# Sheet2.net
KiCad netlist of a schematic drawn in Altium Designer
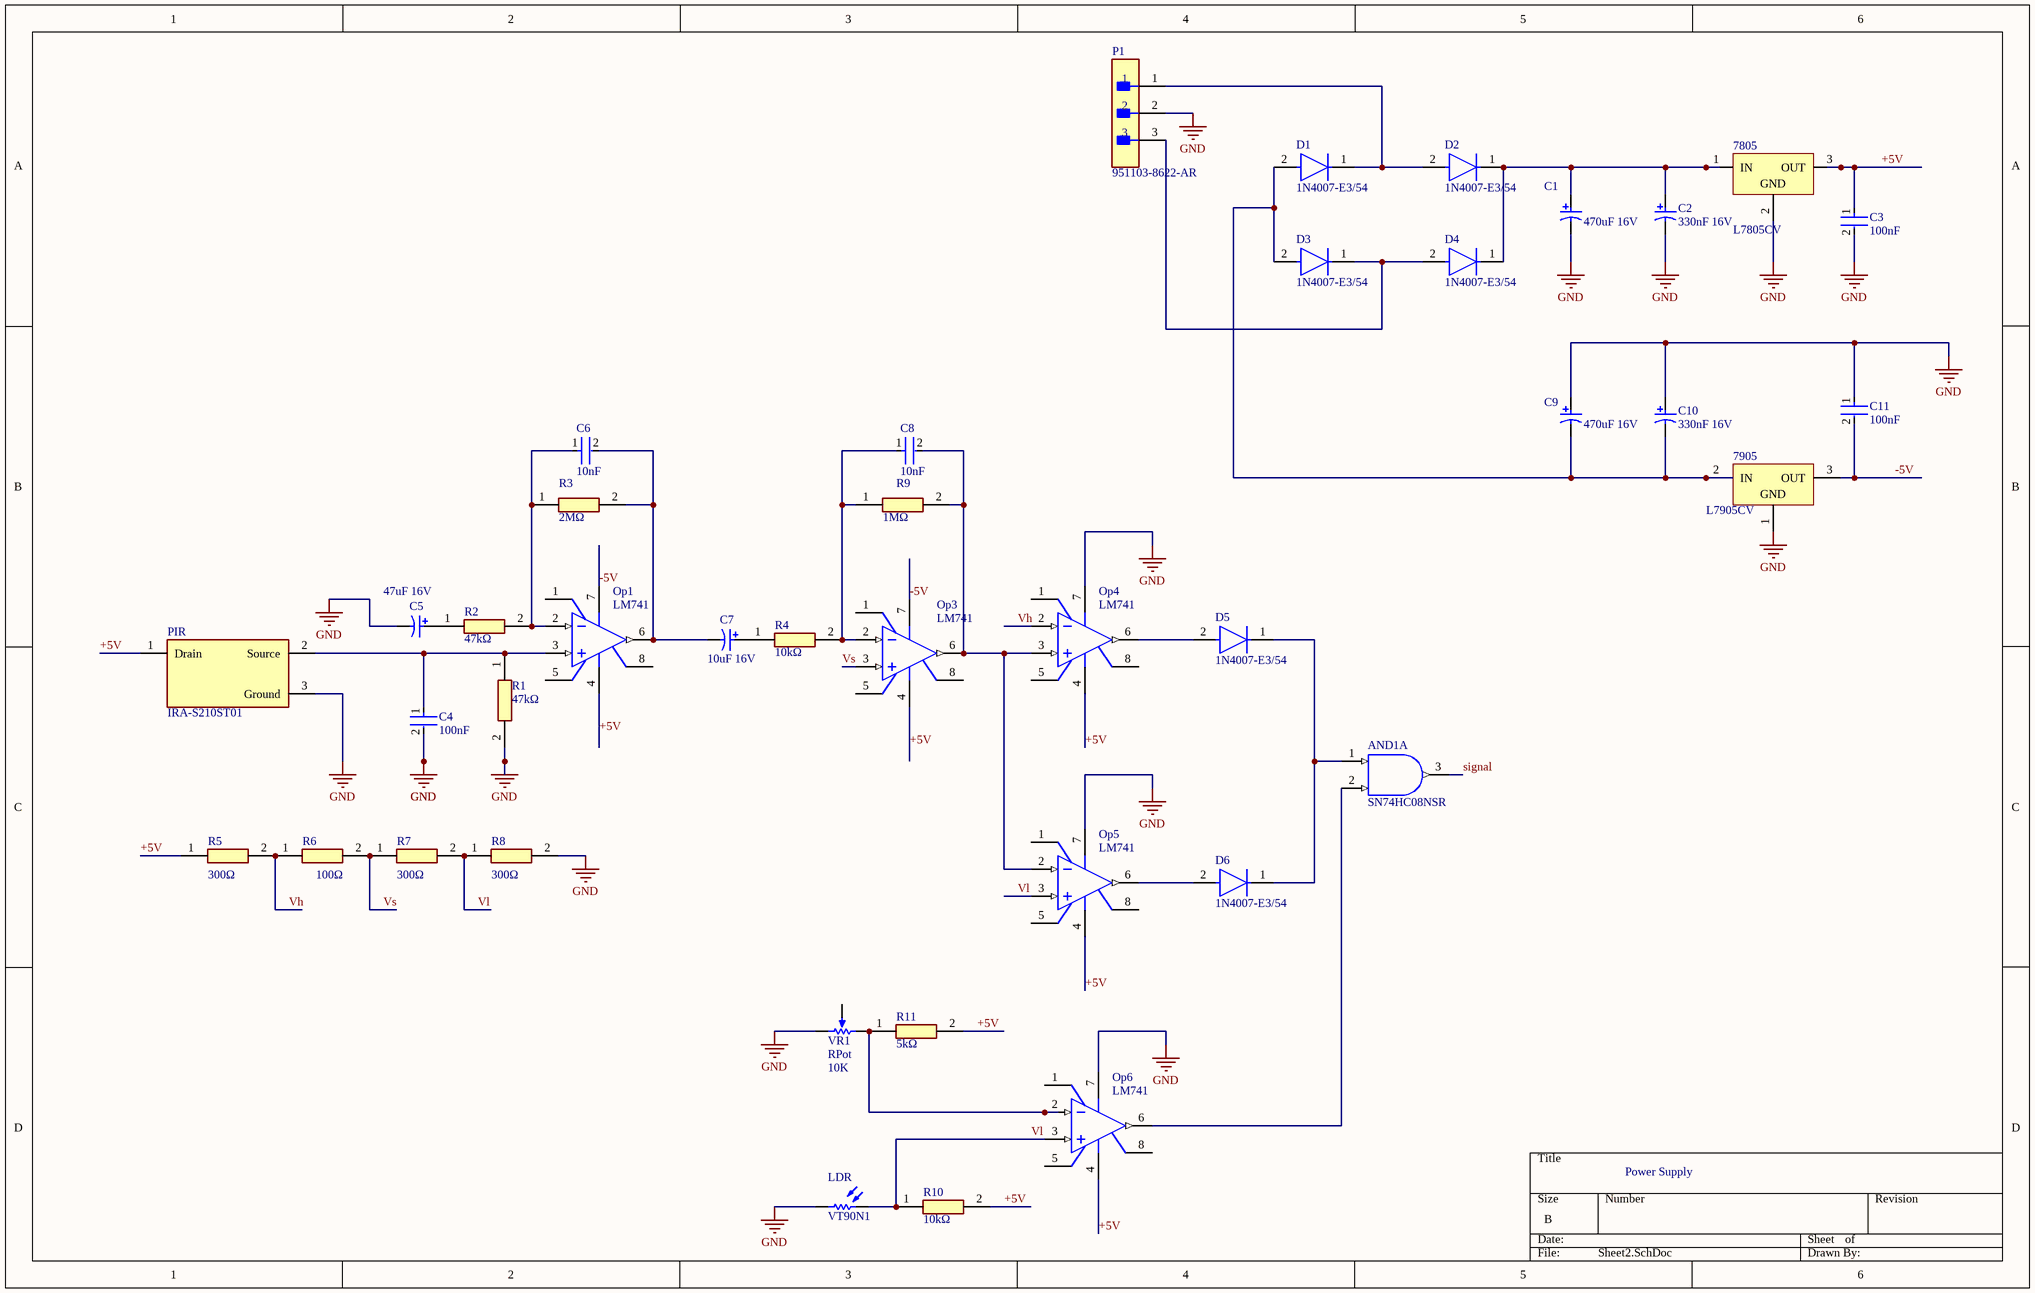
[diagram p0: Sheet2.SchDoc]

(export (version "E")
  (design (tool "Eeschema 10.0.6"))
  (components
    (comp (ref "7805")
      (value "L7805CV")
      (footprint "TO220")
      (description "Positive Voltage Regulator, 5V, 3-Pin TO-220")
      (libsource (lib "Altium Content Vault") (part "PM-REG-L4940-SIL3"))
    )
    (comp (ref "7905")
      (value "L7905CV")
      (footprint "TO-220")
      (description "Negative Voltage Regulator, -5V, 3-Pin TO-220")
      (libsource (lib "Altium Content Vault") (part "PM-REG-7905-SIL3"))
    )
    (comp (ref "AND1")
      (value "SN74HC08NSR")
      (footprint "NS0014A_M")
      (description "Quadruple 2-Input Positive-AND Gates, NS0014A, LARGE T&R")
      (fields
        (field (name "GENERIC PART NUMBER") "SN74HC08")
        (field (name "MANUFACTURER") "Texas Instruments")
      )
      (libsource (lib "Altium Content Vault") (part "TI-AND-4-2IN-14"))
    )
    (comp (ref "C1")
      (value "470uF 16V")
      (footprint "CAPPR65-350-1150X800X1250")
      (description "Aluminum Electrolytic Capacitor, 100 uF, +/- 20%, 50 V, -40 to 85 degC, 2-Pin THD, RoHS, Bulk")
      (fields (field (name "MANUFACTURER") "Panasonic") (field (name "VOLTAGE") "50V"))
      (libsource (lib "Altium Content Vault") (part "CAP-P-2"))
    )
    (comp (ref "C2")
      (value "330nF 16V")
      (footprint "CAPPR65-350-1150X800X1250")
      (description "Aluminum Electrolytic Capacitor, 100 uF, +/- 20%, 50 V, -40 to 85 degC, 2-Pin THD, RoHS, Bulk")
      (fields (field (name "MANUFACTURER") "Panasonic") (field (name "VOLTAGE") "50V"))
      (libsource (lib "Altium Content Vault") (part "CAP-P-2"))
    )
    (comp (ref "C3")
      (value "100nF")
      (footprint "FP-K15H5-MFG")
      (description "CAP CER 0.1UF 50V X7R RADIAL")
      (fields (field (name "VOLTAGE") "50V") (field (name "TOLERANCE") "10%"))
      (libsource (lib "Altium Content Vault") (part "11868f565c42a9108669ba33697ecf6"))
    )
    (comp (ref "C4")
      (value "100nF")
      (footprint "FP-K15H5-MFG")
      (description "CAP CER 0.1UF 50V X7R RADIAL")
      (fields (field (name "VOLTAGE") "50V") (field (name "TOLERANCE") "10%"))
      (libsource (lib "Altium Content Vault") (part "11868f565c42a9108669ba33697ecf6"))
    )
    (comp (ref "C5")
      (value "47uF 16V")
      (footprint "CAPPR65-350-1150X800X1250")
      (description "Aluminum Electrolytic Capacitor, 100 uF, +/- 20%, 50 V, -40 to 85 degC, 2-Pin THD, RoHS, Bulk")
      (fields (field (name "MANUFACTURER") "Panasonic") (field (name "VOLTAGE") "50V"))
      (libsource (lib "Altium Content Vault") (part "CAP-P-2"))
    )
    (comp (ref "C6")
      (value "10nF")
      (footprint "FP-K15H5-MFG")
      (description "CAP CER 0.1UF 50V X7R RADIAL")
      (fields (field (name "VOLTAGE") "50V") (field (name "TOLERANCE") "10%"))
      (libsource (lib "Altium Content Vault") (part "11868f565c42a9108669ba33697ecf6"))
    )
    (comp (ref "C7")
      (value "10uF 16V")
      (footprint "CAPPR65-350-1150X800X1250")
      (description "Aluminum Electrolytic Capacitor, 100 uF, +/- 20%, 50 V, -40 to 85 degC, 2-Pin THD, RoHS, Bulk")
      (fields (field (name "MANUFACTURER") "Panasonic") (field (name "VOLTAGE") "50V"))
      (libsource (lib "Altium Content Vault") (part "CAP-P-2"))
    )
    (comp (ref "C8")
      (value "10nF")
      (footprint "FP-K15H5-MFG")
      (description "CAP CER 0.1UF 50V X7R RADIAL")
      (fields (field (name "VOLTAGE") "50V") (field (name "TOLERANCE") "10%"))
      (libsource (lib "Altium Content Vault") (part "11868f565c42a9108669ba33697ecf6"))
    )
    (comp (ref "C9")
      (value "470uF 16V")
      (footprint "CAPPR65-350-1150X800X1250")
      (description "Aluminum Electrolytic Capacitor, 100 uF, +/- 20%, 50 V, -40 to 85 degC, 2-Pin THD, RoHS, Bulk")
      (fields (field (name "MANUFACTURER") "Panasonic") (field (name "VOLTAGE") "50V"))
      (libsource (lib "Altium Content Vault") (part "CAP-P-2"))
    )
    (comp (ref "C10")
      (value "330nF 16V")
      (footprint "CAPPR65-350-1150X800X1250")
      (description "Aluminum Electrolytic Capacitor, 100 uF, +/- 20%, 50 V, -40 to 85 degC, 2-Pin THD, RoHS, Bulk")
      (fields (field (name "MANUFACTURER") "Panasonic") (field (name "VOLTAGE") "50V"))
      (libsource (lib "Altium Content Vault") (part "CAP-P-2"))
    )
    (comp (ref "C11")
      (value "100nF")
      (footprint "FP-K15H5-MFG")
      (description "CAP CER 0.1UF 50V X7R RADIAL")
      (fields (field (name "VOLTAGE") "50V") (field (name "TOLERANCE") "10%"))
      (libsource (lib "Altium Content Vault") (part "11868f565c42a9108669ba33697ecf6"))
    )
    (comp (ref "D1")
      (value "1N4007-E3/54")
      (footprint "FP-1N4007-MFG")
      (description "DIODE GEN PURP 1KV 1A DO204AL")
      (fields
        (field (name "OCTOPART") "https://octopart.com/1n4007-e3%2F54-vishay-39548207")
        (field (name "MANUFACTURER") "Vishay")
      )
      (libsource (lib "Altium Content Vault") (part "d7152d700b627762746794eb795d46e"))
    )
    (comp (ref "D2")
      (value "1N4007-E3/54")
      (footprint "FP-1N4007-MFG")
      (description "DIODE GEN PURP 1KV 1A DO204AL")
      (fields
        (field (name "OCTOPART") "https://octopart.com/1n4007-e3%2F54-vishay-39548207")
        (field (name "MANUFACTURER") "Vishay")
      )
      (libsource (lib "Altium Content Vault") (part "d7152d700b627762746794eb795d46e"))
    )
    (comp (ref "D3")
      (value "1N4007-E3/54")
      (footprint "FP-1N4007-MFG")
      (description "DIODE GEN PURP 1KV 1A DO204AL")
      (fields
        (field (name "OCTOPART") "https://octopart.com/1n4007-e3%2F54-vishay-39548207")
        (field (name "MANUFACTURER") "Vishay")
      )
      (libsource (lib "Altium Content Vault") (part "d7152d700b627762746794eb795d46e"))
    )
    (comp (ref "D4")
      (value "1N4007-E3/54")
      (footprint "FP-1N4007-MFG")
      (description "DIODE GEN PURP 1KV 1A DO204AL")
      (fields
        (field (name "OCTOPART") "https://octopart.com/1n4007-e3%2F54-vishay-39548207")
        (field (name "MANUFACTURER") "Vishay")
      )
      (libsource (lib "Altium Content Vault") (part "d7152d700b627762746794eb795d46e"))
    )
    (comp (ref "D5")
      (value "1N4007-E3/54")
      (footprint "FP-1N4007-MFG")
      (description "DIODE GEN PURP 1KV 1A DO204AL")
      (fields
        (field (name "OCTOPART") "https://octopart.com/1n4007-e3%2F54-vishay-39548207")
        (field (name "MANUFACTURER") "Vishay")
      )
      (libsource (lib "Altium Content Vault") (part "d7152d700b627762746794eb795d46e"))
    )
    (comp (ref "D6")
      (value "1N4007-E3/54")
      (footprint "FP-1N4007-MFG")
      (description "DIODE GEN PURP 1KV 1A DO204AL")
      (fields
        (field (name "OCTOPART") "https://octopart.com/1n4007-e3%2F54-vishay-39548207")
        (field (name "MANUFACTURER") "Vishay")
      )
      (libsource (lib "Altium Content Vault") (part "d7152d700b627762746794eb795d46e"))
    )
    (comp (ref "LDR")
      (value "VT90N1")
      (footprint "EXCE-VT90N1")
      (description "Photoconductive Resistor, 200 kOhm, 100 V, 80 mW, -40 to 75 degC, 2-Pin THD, RoHS")
      (fields (field (name "MANUFACTURER") "Excelitas Technology"))
      (libsource (lib "Altium Content Vault") (part "PHOTO-RES-2"))
    )
    (comp (ref "Op1")
      (value "LM741")
      (footprint "P0008A")
      (description "Operational Amplifier, 8-pin MDIP, Pb-Free")
      (fields (field (name "MANUFACTURER") "Texas Instruments"))
      (libsource (lib "Altium Content Vault") (part "AMP-OPA-LM741-8"))
    )
    (comp (ref "Op3")
      (value "LM741")
      (footprint "P0008A")
      (description "Operational Amplifier, 8-pin MDIP, Pb-Free")
      (fields (field (name "MANUFACTURER") "Texas Instruments"))
      (libsource (lib "Altium Content Vault") (part "AMP-OPA-LM741-8"))
    )
    (comp (ref "Op4")
      (value "LM741")
      (footprint "P0008A")
      (description "Operational Amplifier, 8-pin MDIP, Pb-Free")
      (fields (field (name "MANUFACTURER") "Texas Instruments"))
      (libsource (lib "Altium Content Vault") (part "AMP-OPA-LM741-8"))
    )
    (comp (ref "Op5")
      (value "LM741")
      (footprint "P0008A")
      (description "Operational Amplifier, 8-pin MDIP, Pb-Free")
      (fields (field (name "MANUFACTURER") "Texas Instruments"))
      (libsource (lib "Altium Content Vault") (part "AMP-OPA-LM741-8"))
    )
    (comp (ref "Op6")
      (value "LM741")
      (footprint "P0008A")
      (description "Operational Amplifier, 8-pin MDIP, Pb-Free")
      (fields (field (name "MANUFACTURER") "Texas Instruments"))
      (libsource (lib "Altium Content Vault") (part "AMP-OPA-LM741-8"))
    )
    (comp (ref "P1")
      (value "951103-8622-AR")
      (footprint "FP-951103-8622-AR-MFG")
      (description "CONN HEADER VERT 3POS 2MM")
      (fields
        (field (name "OCTOPART") "https://octopart.com/951103-8622-ar-3m-14400669")
        (field (name "MANUFACTURER") "3M")
      )
      (libsource (lib "Altium Content Vault") (part "0d3f023dd272f625e17a2be33dea85f"))
    )
    (comp (ref "PIR")
      (value "IRA-S210ST01")
      (footprint "FP-IRA-S210ST01-MFG")
      (description "MOTION SENSOR")
      (fields
        (field (name "OCTOPART") "https://octopart.com/ira-s210st01-murata-30987376")
        (field (name "MANUFACTURER") "Murata")
      )
      (libsource (lib "Altium Content Vault") (part "808bf1407e63c16d253ccb095fe1426"))
    )
    (comp (ref "R1")
      (value "47kΩ")
      (footprint "SamacSys:RESAD1650W60L650D250")
      (description "Resistor")
      (fields
        (field (name "MANUFACTURER_PART_NUMBER") "MRS25000C1002FC100")
        (field (name "MOUSER PART NUMBER") "594-2322-156-11003")
      )
      (libsource (lib "") (part "MRS25000C1002FC100_1"))
    )
    (comp (ref "R2")
      (value "47kΩ")
      (footprint "SamacSys:RESAD1650W60L650D250")
      (description "Resistor")
      (fields
        (field (name "MANUFACTURER_PART_NUMBER") "MRS25000C1002FC100")
        (field (name "MOUSER PART NUMBER") "594-2322-156-11003")
      )
      (libsource (lib "*") (part "MRS25000C1002FC100"))
    )
    (comp (ref "R3")
      (value "2MΩ")
      (footprint "SamacSys:RESAD1650W60L650D250")
      (description "Resistor")
      (fields
        (field (name "MANUFACTURER_PART_NUMBER") "MRS25000C1002FC100")
        (field (name "MOUSER PART NUMBER") "594-2322-156-11003")
      )
      (libsource (lib "*") (part "MRS25000C1002FC100"))
    )
    (comp (ref "R4")
      (value "10kΩ")
      (footprint "SamacSys:RESAD1650W60L650D250")
      (description "Resistor")
      (fields
        (field (name "MANUFACTURER_PART_NUMBER") "MRS25000C1002FC100")
        (field (name "MOUSER PART NUMBER") "594-2322-156-11003")
      )
      (libsource (lib "*") (part "MRS25000C1002FC100"))
    )
    (comp (ref "R5")
      (value "300Ω")
      (footprint "SamacSys:RESAD1650W60L650D250")
      (description "Resistor")
      (fields
        (field (name "MANUFACTURER_PART_NUMBER") "MRS25000C1002FC100")
        (field (name "MOUSER PART NUMBER") "594-2322-156-11003")
      )
      (libsource (lib "*") (part "MRS25000C1002FC100"))
    )
    (comp (ref "R6")
      (value "100Ω")
      (footprint "SamacSys:RESAD1650W60L650D250")
      (description "Resistor")
      (fields
        (field (name "MANUFACTURER_PART_NUMBER") "MRS25000C1002FC100")
        (field (name "MOUSER PART NUMBER") "594-2322-156-11003")
      )
      (libsource (lib "*") (part "MRS25000C1002FC100"))
    )
    (comp (ref "R7")
      (value "300Ω")
      (footprint "SamacSys:RESAD1650W60L650D250")
      (description "Resistor")
      (fields
        (field (name "MANUFACTURER_PART_NUMBER") "MRS25000C1002FC100")
        (field (name "MOUSER PART NUMBER") "594-2322-156-11003")
      )
      (libsource (lib "*") (part "MRS25000C1002FC100"))
    )
    (comp (ref "R8")
      (value "300Ω")
      (footprint "SamacSys:RESAD1650W60L650D250")
      (description "Resistor")
      (fields
        (field (name "MANUFACTURER_PART_NUMBER") "MRS25000C1002FC100")
        (field (name "MOUSER PART NUMBER") "594-2322-156-11003")
      )
      (libsource (lib "*") (part "MRS25000C1002FC100"))
    )
    (comp (ref "R9")
      (value "1MΩ")
      (footprint "SamacSys:RESAD1650W60L650D250")
      (description "Resistor")
      (fields
        (field (name "MANUFACTURER_PART_NUMBER") "MRS25000C1002FC100")
        (field (name "MOUSER PART NUMBER") "594-2322-156-11003")
      )
      (libsource (lib "*") (part "MRS25000C1002FC100"))
    )
    (comp (ref "R10")
      (value "10kΩ")
      (footprint "SamacSys:RESAD1650W60L650D250")
      (description "Resistor")
      (fields
        (field (name "MANUFACTURER_PART_NUMBER") "MRS25000C1002FC100")
        (field (name "MOUSER PART NUMBER") "594-2322-156-11003")
      )
      (libsource (lib "*") (part "MRS25000C1002FC100"))
    )
    (comp (ref "R11")
      (value "5kΩ")
      (footprint "SamacSys:RESAD1650W60L650D250")
      (description "Resistor")
      (fields
        (field (name "MANUFACTURER_PART_NUMBER") "MRS25000C1002FC100")
        (field (name "MOUSER PART NUMBER") "594-2322-156-11003")
      )
      (libsource (lib "*") (part "MRS25000C1002FC100"))
    )
    (comp (ref "VR1")
      (value "RPot")
      (footprint "VR5")
      (description "Potentiometer")
      (fields (field (name "ALTIUM_VALUE") "10K") (field (name "PUBLISHER") "Altium Limited"))
      (libsource (lib "Miscellaneous Devices") (part "RPot"))
    )
  )
  (nets
    (net (code "1") (name "/+5V") (class "Default")
      (node (ref "7805") (pin "3") (pinfunction "OUT_3") (pintype "power_in"))
      (node (ref "C3") (pin "1") (pinfunction "1_1") (pintype "passive"))
      (node (ref "Op1") (pin "4") (pinfunction "V-_4") (pintype "power_in"))
      (node (ref "Op3") (pin "4") (pinfunction "V-_4") (pintype "power_in"))
      (node (ref "Op4") (pin "4") (pinfunction "V-_4") (pintype "power_in"))
      (node (ref "Op5") (pin "4") (pinfunction "V-_4") (pintype "power_in"))
      (node (ref "Op6") (pin "4") (pinfunction "V-_4") (pintype "power_in"))
      (node (ref "PIR") (pin "1") (pinfunction "Drain_1") (pintype "passive"))
      (node (ref "R10") (pin "2") (pinfunction "2_2") (pintype "passive"))
      (node (ref "R11") (pin "2") (pinfunction "2_2") (pintype "passive"))
      (node (ref "R5") (pin "1") (pinfunction "1_1") (pintype "passive"))
    )
    (net (code "2") (name "/-5V") (class "Default")
      (node (ref "7905") (pin "3") (pinfunction "OUT_3") (pintype "power_in"))
      (node (ref "C11") (pin "2") (pinfunction "2_2") (pintype "passive"))
      (node (ref "Op1") (pin "7") (pinfunction "V+_7") (pintype "power_in"))
      (node (ref "Op3") (pin "7") (pinfunction "V+_7") (pintype "power_in"))
    )
    (net (code "4") (name "/Vh") (class "Default")
      (node (ref "Op4") (pin "2") (pinfunction "IN-_2") (pintype "input"))
      (node (ref "R5") (pin "2") (pinfunction "2_2") (pintype "passive"))
      (node (ref "R6") (pin "1") (pinfunction "1_1") (pintype "passive"))
    )
    (net (code "5") (name "/Vl") (class "Default")
      (node (ref "LDR") (pin "2") (pinfunction "2_2") (pintype "passive"))
      (node (ref "Op5") (pin "3") (pinfunction "IN+_3") (pintype "input"))
      (node (ref "Op6") (pin "3") (pinfunction "IN+_3") (pintype "input"))
      (node (ref "R10") (pin "1") (pinfunction "1_1") (pintype "passive"))
      (node (ref "R7") (pin "2") (pinfunction "2_2") (pintype "passive"))
      (node (ref "R8") (pin "1") (pinfunction "1_1") (pintype "passive"))
    )
    (net (code "6") (name "/Vs") (class "Default")
      (node (ref "Op3") (pin "3") (pinfunction "IN+_3") (pintype "input"))
      (node (ref "R6") (pin "2") (pinfunction "2_2") (pintype "passive"))
      (node (ref "R7") (pin "1") (pinfunction "1_1") (pintype "passive"))
    )
    (net (code "7") (name "/signal") (class "Default")
      (node (ref "AND1") (pin "3") (pinfunction "1Y_3") (pintype "output"))
    )
    (net (code "8") (name "GND") (class "Default")
      (node (ref "7805") (pin "2") (pinfunction "GND_2") (pintype "power_in"))
      (node (ref "7905") (pin "1") (pinfunction "GND_1") (pintype "power_in"))
      (node (ref "C1") (pin "2") (pinfunction "2_2") (pintype "passive"))
      (node (ref "C10") (pin "1") (pinfunction "1_1") (pintype "passive"))
      (node (ref "C11") (pin "1") (pinfunction "1_1") (pintype "passive"))
      (node (ref "C2") (pin "2") (pinfunction "2_2") (pintype "passive"))
      (node (ref "C3") (pin "2") (pinfunction "2_2") (pintype "passive"))
      (node (ref "C4") (pin "2") (pinfunction "2_2") (pintype "passive"))
      (node (ref "C5") (pin "2") (pinfunction "2_2") (pintype "passive"))
      (node (ref "C9") (pin "1") (pinfunction "1_1") (pintype "passive"))
      (node (ref "LDR") (pin "1") (pinfunction "1_1") (pintype "passive"))
      (node (ref "Op4") (pin "7") (pinfunction "V+_7") (pintype "power_in"))
      (node (ref "Op5") (pin "7") (pinfunction "V+_7") (pintype "power_in"))
      (node (ref "Op6") (pin "7") (pinfunction "V+_7") (pintype "power_in"))
      (node (ref "P1") (pin "2") (pinfunction "2_2") (pintype "passive"))
      (node (ref "PIR") (pin "3") (pinfunction "Ground_3") (pintype "power_in"))
      (node (ref "R1") (pin "2") (pinfunction "2_2") (pintype "passive"))
      (node (ref "R8") (pin "2") (pinfunction "2_2") (pintype "passive"))
      (node (ref "VR1") (pin "2") (pinfunction "BOT_2") (pintype "passive"))
    )
    (net (code "9") (name "Net-(7805-IN)") (class "Default")
      (node (ref "7805") (pin "1") (pinfunction "IN_1") (pintype "power_in"))
      (node (ref "C1") (pin "1") (pinfunction "1_1") (pintype "passive"))
      (node (ref "C2") (pin "1") (pinfunction "1_1") (pintype "passive"))
      (node (ref "D2") (pin "1") (pinfunction "C_1") (pintype "passive"))
      (node (ref "D4") (pin "1") (pinfunction "C_1") (pintype "passive"))
    )
    (net (code "10") (name "Net-(7905-IN)") (class "Default")
      (node (ref "7905") (pin "2") (pinfunction "IN_2") (pintype "power_in"))
      (node (ref "C10") (pin "2") (pinfunction "2_2") (pintype "passive"))
      (node (ref "C9") (pin "2") (pinfunction "2_2") (pintype "passive"))
      (node (ref "D1") (pin "2") (pinfunction "A_2") (pintype "passive"))
      (node (ref "D3") (pin "2") (pinfunction "A_2") (pintype "passive"))
    )
    (net (code "11") (name "Net-(AND1A-1A)") (class "Default")
      (node (ref "AND1") (pin "1") (pinfunction "1A_1") (pintype "input"))
      (node (ref "D5") (pin "1") (pinfunction "C_1") (pintype "passive"))
      (node (ref "D6") (pin "1") (pinfunction "C_1") (pintype "passive"))
    )
    (net (code "12") (name "Net-(AND1A-1B)") (class "Default")
      (node (ref "AND1") (pin "2") (pinfunction "1B_2") (pintype "input"))
      (node (ref "Op6") (pin "6") (pinfunction "OUT_6") (pintype "output"))
    )
    (net (code "13") (name "Net-(C5-Pad1)") (class "Default")
      (node (ref "C5") (pin "1") (pinfunction "1_1") (pintype "passive"))
      (node (ref "R2") (pin "1") (pinfunction "1_1") (pintype "passive"))
    )
    (net (code "14") (name "Net-(C7-Pad1)") (class "Default")
      (node (ref "C7") (pin "1") (pinfunction "1_1") (pintype "passive"))
      (node (ref "R4") (pin "1") (pinfunction "1_1") (pintype "passive"))
    )
    (net (code "15") (name "Net-(D1-C)") (class "Default")
      (node (ref "D1") (pin "1") (pinfunction "C_1") (pintype "passive"))
      (node (ref "D2") (pin "2") (pinfunction "A_2") (pintype "passive"))
      (node (ref "P1") (pin "1") (pinfunction "1_1") (pintype "passive"))
    )
    (net (code "16") (name "Net-(D3-C)") (class "Default")
      (node (ref "D3") (pin "1") (pinfunction "C_1") (pintype "passive"))
      (node (ref "D4") (pin "2") (pinfunction "A_2") (pintype "passive"))
      (node (ref "P1") (pin "3") (pinfunction "3_3") (pintype "passive"))
    )
    (net (code "17") (name "Net-(D5-A)") (class "Default")
      (node (ref "D5") (pin "2") (pinfunction "A_2") (pintype "passive"))
      (node (ref "Op4") (pin "6") (pinfunction "OUT_6") (pintype "output"))
    )
    (net (code "18") (name "Net-(D6-A)") (class "Default")
      (node (ref "D6") (pin "2") (pinfunction "A_2") (pintype "passive"))
      (node (ref "Op5") (pin "6") (pinfunction "OUT_6") (pintype "output"))
    )
    (net (code "19") (name "Net-(Op1-IN+)") (class "Default")
      (node (ref "C4") (pin "1") (pinfunction "1_1") (pintype "passive"))
      (node (ref "Op1") (pin "3") (pinfunction "IN+_3") (pintype "input"))
      (node (ref "PIR") (pin "2") (pinfunction "Source_2") (pintype "passive"))
      (node (ref "R1") (pin "1") (pinfunction "1_1") (pintype "passive"))
    )
    (net (code "20") (name "Net-(Op1-IN-)") (class "Default")
      (node (ref "C6") (pin "1") (pinfunction "1_1") (pintype "passive"))
      (node (ref "Op1") (pin "2") (pinfunction "IN-_2") (pintype "input"))
      (node (ref "R2") (pin "2") (pinfunction "2_2") (pintype "passive"))
      (node (ref "R3") (pin "1") (pinfunction "1_1") (pintype "passive"))
    )
    (net (code "21") (name "Net-(Op1-OUT)") (class "Default")
      (node (ref "C6") (pin "2") (pinfunction "2_2") (pintype "passive"))
      (node (ref "C7") (pin "2") (pinfunction "2_2") (pintype "passive"))
      (node (ref "Op1") (pin "6") (pinfunction "OUT_6") (pintype "output"))
      (node (ref "R3") (pin "2") (pinfunction "2_2") (pintype "passive"))
    )
    (net (code "22") (name "Net-(Op3-IN-)") (class "Default")
      (node (ref "C8") (pin "1") (pinfunction "1_1") (pintype "passive"))
      (node (ref "Op3") (pin "2") (pinfunction "IN-_2") (pintype "input"))
      (node (ref "R4") (pin "2") (pinfunction "2_2") (pintype "passive"))
      (node (ref "R9") (pin "1") (pinfunction "1_1") (pintype "passive"))
    )
    (net (code "23") (name "Net-(Op3-OUT)") (class "Default")
      (node (ref "C8") (pin "2") (pinfunction "2_2") (pintype "passive"))
      (node (ref "Op3") (pin "6") (pinfunction "OUT_6") (pintype "output"))
      (node (ref "Op4") (pin "3") (pinfunction "IN+_3") (pintype "input"))
      (node (ref "Op5") (pin "2") (pinfunction "IN-_2") (pintype "input"))
      (node (ref "R9") (pin "2") (pinfunction "2_2") (pintype "passive"))
    )
    (net (code "24") (name "Net-(Op6-IN-)") (class "Default")
      (node (ref "Op6") (pin "2") (pinfunction "IN-_2") (pintype "input"))
      (node (ref "R11") (pin "1") (pinfunction "1_1") (pintype "passive"))
      (node (ref "VR1") (pin "1") (pinfunction "TOP_1") (pintype "passive"))
    )
    (net (code "25") (name "unconnected-(Op1-NC-Pad8)") (class "Default")
      (node (ref "Op1") (pin "8") (pinfunction "NC_8") (pintype "passive"))
    )
    (net (code "26") (name "unconnected-(Op1-OFS_NULL-Pad1)") (class "Default")
      (node (ref "Op1") (pin "1") (pinfunction "OFS_NULL_1") (pintype "passive"))
    )
    (net (code "27") (name "unconnected-(Op1-OFS_NULL-Pad5)") (class "Default")
      (node (ref "Op1") (pin "5") (pinfunction "OFS_NULL_5") (pintype "passive"))
    )
    (net (code "28") (name "unconnected-(Op3-NC-Pad8)") (class "Default")
      (node (ref "Op3") (pin "8") (pinfunction "NC_8") (pintype "passive"))
    )
    (net (code "29") (name "unconnected-(Op3-OFS_NULL-Pad1)") (class "Default")
      (node (ref "Op3") (pin "1") (pinfunction "OFS_NULL_1") (pintype "passive"))
    )
    (net (code "30") (name "unconnected-(Op3-OFS_NULL-Pad5)") (class "Default")
      (node (ref "Op3") (pin "5") (pinfunction "OFS_NULL_5") (pintype "passive"))
    )
    (net (code "31") (name "unconnected-(Op4-NC-Pad8)") (class "Default")
      (node (ref "Op4") (pin "8") (pinfunction "NC_8") (pintype "passive"))
    )
    (net (code "32") (name "unconnected-(Op4-OFS_NULL-Pad1)") (class "Default")
      (node (ref "Op4") (pin "1") (pinfunction "OFS_NULL_1") (pintype "passive"))
    )
    (net (code "33") (name "unconnected-(Op4-OFS_NULL-Pad5)") (class "Default")
      (node (ref "Op4") (pin "5") (pinfunction "OFS_NULL_5") (pintype "passive"))
    )
    (net (code "34") (name "unconnected-(Op5-NC-Pad8)") (class "Default")
      (node (ref "Op5") (pin "8") (pinfunction "NC_8") (pintype "passive"))
    )
    (net (code "35") (name "unconnected-(Op5-OFS_NULL-Pad1)") (class "Default")
      (node (ref "Op5") (pin "1") (pinfunction "OFS_NULL_1") (pintype "passive"))
    )
    (net (code "36") (name "unconnected-(Op5-OFS_NULL-Pad5)") (class "Default")
      (node (ref "Op5") (pin "5") (pinfunction "OFS_NULL_5") (pintype "passive"))
    )
    (net (code "37") (name "unconnected-(Op6-NC-Pad8)") (class "Default")
      (node (ref "Op6") (pin "8") (pinfunction "NC_8") (pintype "passive"))
    )
    (net (code "38") (name "unconnected-(Op6-OFS_NULL-Pad1)") (class "Default")
      (node (ref "Op6") (pin "1") (pinfunction "OFS_NULL_1") (pintype "passive"))
    )
    (net (code "39") (name "unconnected-(Op6-OFS_NULL-Pad5)") (class "Default")
      (node (ref "Op6") (pin "5") (pinfunction "OFS_NULL_5") (pintype "passive"))
    )
    (net (code "40") (name "unconnected-(VR1-TAP-Pad3)") (class "Default")
      (node (ref "VR1") (pin "3") (pinfunction "TAP_3") (pintype "passive"))
    )
  )
)
